# InterfacesA_Decoupling.net
KiCad netlist of a schematic drawn in Altium Designer
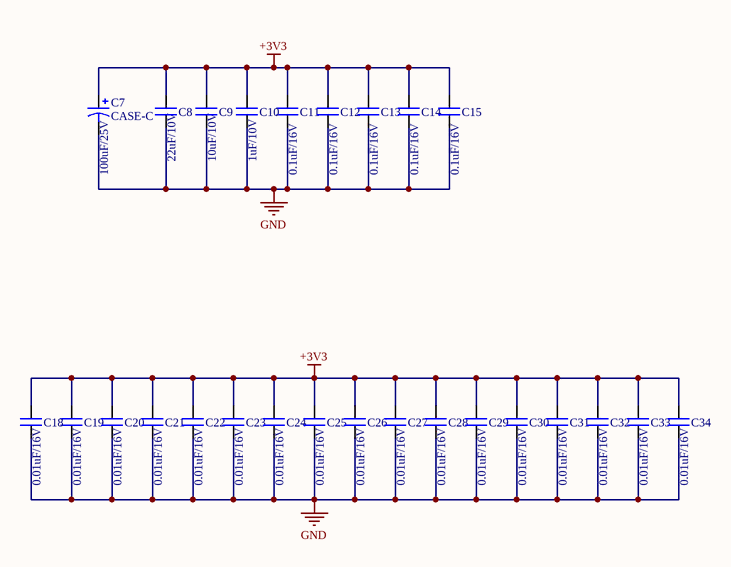
[diagram p0: InterfacesA_Decoupling.SchDoc]

(export (version "E")
  (design (tool "Eeschema 10.0.6"))
  (components
    (comp (ref "C7")
      (value "CASE-C")
      (footprint "CASE-C")
      (fields (field (name "ALTIUM_VALUE") "100uF/25V"))
      (libsource (lib "AdapterLib") (part "CASE-C"))
    )
    (comp (ref "C8")
      (value "22uF/10V")
      (footprint "CAP_0805")
      (fields (field (name "Comment") "CAP_0805"))
      (libsource (lib "AdapterLib") (part "CAP_0805"))
    )
    (comp (ref "C9")
      (value "10uF/10V")
      (footprint "CAP_0805")
      (fields (field (name "Comment") "CAP_0805"))
      (libsource (lib "AdapterLib") (part "CAP_0805"))
    )
    (comp (ref "C10")
      (value "1uF/10V")
      (footprint "CAP_0805")
      (fields (field (name "Comment") "CAP_0805"))
      (libsource (lib "AdapterLib") (part "CAP_0805"))
    )
    (comp (ref "C11")
      (value "0.1uF/16V")
      (footprint "CAP_0805")
      (fields (field (name "Comment") "CAP_0805"))
      (libsource (lib "AdapterLib") (part "CAP_0805"))
    )
    (comp (ref "C12")
      (value "0.1uF/16V")
      (footprint "CAP_0805")
      (fields (field (name "Comment") "CAP_0805"))
      (libsource (lib "AdapterLib") (part "CAP_0805"))
    )
    (comp (ref "C13")
      (value "0.1uF/16V")
      (footprint "CAP_0805")
      (fields (field (name "Comment") "CAP_0805"))
      (libsource (lib "AdapterLib") (part "CAP_0805"))
    )
    (comp (ref "C14")
      (value "0.1uF/16V")
      (footprint "CAP_0805")
      (fields (field (name "Comment") "CAP_0805"))
      (libsource (lib "AdapterLib") (part "CAP_0805"))
    )
    (comp (ref "C15")
      (value "0.1uF/16V")
      (footprint "CAP_0805")
      (fields (field (name "Comment") "CAP_0805"))
      (libsource (lib "AdapterLib") (part "CAP_0805"))
    )
    (comp (ref "C18")
      (value "0.01uF/16V")
      (footprint "CAP_0805")
      (fields (field (name "Comment") "CAP_0805"))
      (libsource (lib "AdapterLib") (part "CAP_0805"))
    )
    (comp (ref "C19")
      (value "0.01uF/16V")
      (footprint "CAP_0805")
      (fields (field (name "Comment") "CAP_0805"))
      (libsource (lib "AdapterLib") (part "CAP_0805"))
    )
    (comp (ref "C20")
      (value "0.01uF/16V")
      (footprint "CAP_0805")
      (fields (field (name "Comment") "CAP_0805"))
      (libsource (lib "AdapterLib") (part "CAP_0805"))
    )
    (comp (ref "C21")
      (value "0.01uF/16V")
      (footprint "CAP_0805")
      (fields (field (name "Comment") "CAP_0805"))
      (libsource (lib "AdapterLib") (part "CAP_0805"))
    )
    (comp (ref "C22")
      (value "0.01uF/16V")
      (footprint "CAP_0805")
      (fields (field (name "Comment") "CAP_0805"))
      (libsource (lib "AdapterLib") (part "CAP_0805"))
    )
    (comp (ref "C23")
      (value "0.01uF/16V")
      (footprint "CAP_0805")
      (fields (field (name "Comment") "CAP_0805"))
      (libsource (lib "AdapterLib") (part "CAP_0805"))
    )
    (comp (ref "C24")
      (value "0.01uF/16V")
      (footprint "CAP_0805")
      (fields (field (name "Comment") "CAP_0805"))
      (libsource (lib "AdapterLib") (part "CAP_0805"))
    )
    (comp (ref "C25")
      (value "0.01uF/16V")
      (footprint "CAP_0805")
      (fields (field (name "Comment") "CAP_0805"))
      (libsource (lib "AdapterLib") (part "CAP_0805"))
    )
    (comp (ref "C26")
      (value "0.01uF/16V")
      (footprint "CAP_0805")
      (fields (field (name "Comment") "CAP_0805"))
      (libsource (lib "AdapterLib") (part "CAP_0805"))
    )
    (comp (ref "C27")
      (value "0.01uF/16V")
      (footprint "CAP_0805")
      (fields (field (name "Comment") "CAP_0805"))
      (libsource (lib "AdapterLib") (part "CAP_0805"))
    )
    (comp (ref "C28")
      (value "0.01uF/16V")
      (footprint "CAP_0805")
      (fields (field (name "Comment") "CAP_0805"))
      (libsource (lib "AdapterLib") (part "CAP_0805"))
    )
    (comp (ref "C29")
      (value "0.01uF/16V")
      (footprint "CAP_0805")
      (fields (field (name "Comment") "CAP_0805"))
      (libsource (lib "AdapterLib") (part "CAP_0805"))
    )
    (comp (ref "C30")
      (value "0.01uF/16V")
      (footprint "CAP_0805")
      (fields (field (name "Comment") "CAP_0805"))
      (libsource (lib "AdapterLib") (part "CAP_0805"))
    )
    (comp (ref "C31")
      (value "0.01uF/16V")
      (footprint "CAP_0805")
      (fields (field (name "Comment") "CAP_0805"))
      (libsource (lib "AdapterLib") (part "CAP_0805"))
    )
    (comp (ref "C32")
      (value "0.01uF/16V")
      (footprint "CAP_0805")
      (fields (field (name "Comment") "CAP_0805"))
      (libsource (lib "AdapterLib") (part "CAP_0805"))
    )
    (comp (ref "C33")
      (value "0.01uF/16V")
      (footprint "CAP_0805")
      (fields (field (name "Comment") "CAP_0805"))
      (libsource (lib "AdapterLib") (part "CAP_0805"))
    )
    (comp (ref "C34")
      (value "0.01uF/16V")
      (footprint "CAP_0805")
      (fields (field (name "Comment") "CAP_0805"))
      (libsource (lib "AdapterLib") (part "CAP_0805"))
    )
  )
  (nets
    (net (code "1") (name "+3V3") (class "Default")
      (node (ref "C10") (pin "2") (pinfunction "2_2") (pintype "passive"))
      (node (ref "C11") (pin "2") (pinfunction "2_2") (pintype "passive"))
      (node (ref "C12") (pin "2") (pinfunction "2_2") (pintype "passive"))
      (node (ref "C13") (pin "2") (pinfunction "2_2") (pintype "passive"))
      (node (ref "C14") (pin "2") (pinfunction "2_2") (pintype "passive"))
      (node (ref "C15") (pin "2") (pinfunction "2_2") (pintype "passive"))
      (node (ref "C18") (pin "2") (pinfunction "2_2") (pintype "passive"))
      (node (ref "C19") (pin "2") (pinfunction "2_2") (pintype "passive"))
      (node (ref "C20") (pin "2") (pinfunction "2_2") (pintype "passive"))
      (node (ref "C21") (pin "2") (pinfunction "2_2") (pintype "passive"))
      (node (ref "C22") (pin "2") (pinfunction "2_2") (pintype "passive"))
      (node (ref "C23") (pin "2") (pinfunction "2_2") (pintype "passive"))
      (node (ref "C24") (pin "2") (pinfunction "2_2") (pintype "passive"))
      (node (ref "C25") (pin "2") (pinfunction "2_2") (pintype "passive"))
      (node (ref "C26") (pin "2") (pinfunction "2_2") (pintype "passive"))
      (node (ref "C27") (pin "2") (pinfunction "2_2") (pintype "passive"))
      (node (ref "C28") (pin "2") (pinfunction "2_2") (pintype "passive"))
      (node (ref "C29") (pin "2") (pinfunction "2_2") (pintype "passive"))
      (node (ref "C30") (pin "2") (pinfunction "2_2") (pintype "passive"))
      (node (ref "C31") (pin "2") (pinfunction "2_2") (pintype "passive"))
      (node (ref "C32") (pin "2") (pinfunction "2_2") (pintype "passive"))
      (node (ref "C33") (pin "2") (pinfunction "2_2") (pintype "passive"))
      (node (ref "C34") (pin "2") (pinfunction "2_2") (pintype "passive"))
      (node (ref "C7") (pin "A") (pinfunction "1_A") (pintype "passive"))
      (node (ref "C8") (pin "2") (pinfunction "2_2") (pintype "passive"))
      (node (ref "C9") (pin "2") (pinfunction "2_2") (pintype "passive"))
    )
    (net (code "2") (name "GND") (class "Default")
      (node (ref "C10") (pin "1") (pinfunction "1_1") (pintype "passive"))
      (node (ref "C11") (pin "1") (pinfunction "1_1") (pintype "passive"))
      (node (ref "C12") (pin "1") (pinfunction "1_1") (pintype "passive"))
      (node (ref "C13") (pin "1") (pinfunction "1_1") (pintype "passive"))
      (node (ref "C14") (pin "1") (pinfunction "1_1") (pintype "passive"))
      (node (ref "C15") (pin "1") (pinfunction "1_1") (pintype "passive"))
      (node (ref "C18") (pin "1") (pinfunction "1_1") (pintype "passive"))
      (node (ref "C19") (pin "1") (pinfunction "1_1") (pintype "passive"))
      (node (ref "C20") (pin "1") (pinfunction "1_1") (pintype "passive"))
      (node (ref "C21") (pin "1") (pinfunction "1_1") (pintype "passive"))
      (node (ref "C22") (pin "1") (pinfunction "1_1") (pintype "passive"))
      (node (ref "C23") (pin "1") (pinfunction "1_1") (pintype "passive"))
      (node (ref "C24") (pin "1") (pinfunction "1_1") (pintype "passive"))
      (node (ref "C25") (pin "1") (pinfunction "1_1") (pintype "passive"))
      (node (ref "C26") (pin "1") (pinfunction "1_1") (pintype "passive"))
      (node (ref "C27") (pin "1") (pinfunction "1_1") (pintype "passive"))
      (node (ref "C28") (pin "1") (pinfunction "1_1") (pintype "passive"))
      (node (ref "C29") (pin "1") (pinfunction "1_1") (pintype "passive"))
      (node (ref "C30") (pin "1") (pinfunction "1_1") (pintype "passive"))
      (node (ref "C31") (pin "1") (pinfunction "1_1") (pintype "passive"))
      (node (ref "C32") (pin "1") (pinfunction "1_1") (pintype "passive"))
      (node (ref "C33") (pin "1") (pinfunction "1_1") (pintype "passive"))
      (node (ref "C34") (pin "1") (pinfunction "1_1") (pintype "passive"))
      (node (ref "C7") (pin "K") (pinfunction "2_K") (pintype "passive"))
      (node (ref "C8") (pin "1") (pinfunction "1_1") (pintype "passive"))
      (node (ref "C9") (pin "1") (pinfunction "1_1") (pintype "passive"))
    )
  )
)
